# IAIf1Doc.net
KiCad netlist of a schematic drawn in Altium Designer
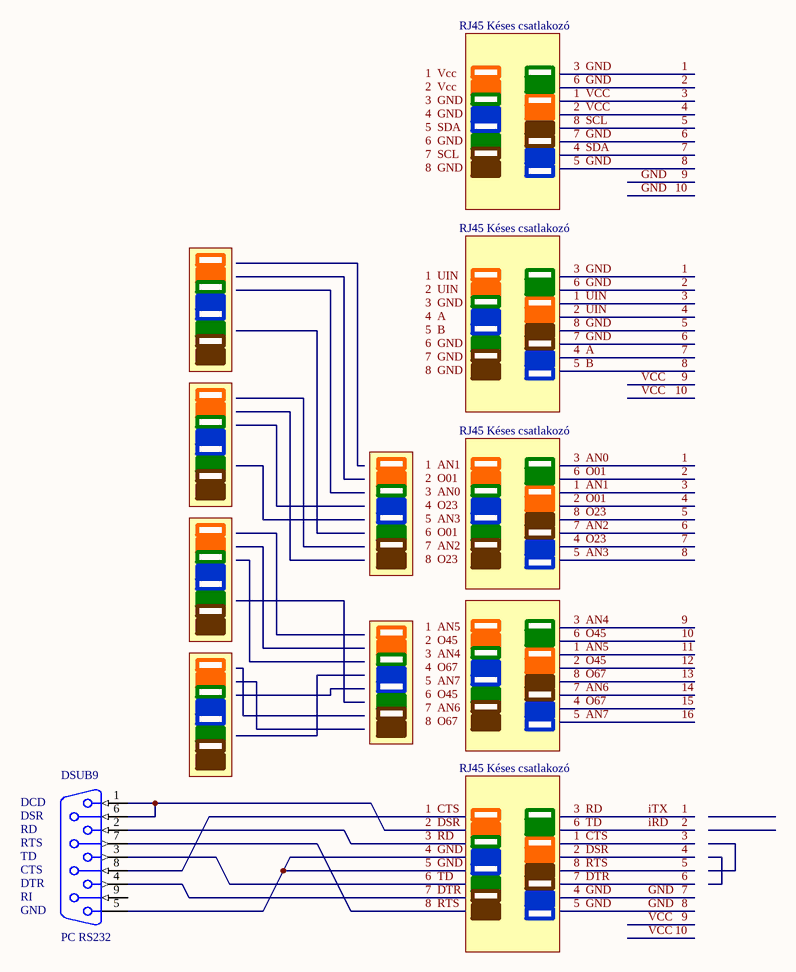
[diagram p0: IAIf1Doc.SchDoc]

(export (version "E")
  (design (tool "Eeschema 10.0.6"))
  (components
    (comp (ref "DSUB9")
      (value "PC RS232")
      (footprint "DSUB1.385-2H9")
      (description "Receptacle Assembly, 9 Position, Right Angle")
      (fields (field (name "PUBLISHER") "Altium Limited"))
      (libsource (lib "Miscellaneous Connectors") (part "D Connector 9"))
    )
  )
  (nets
    (net (code "1") (name "/1") (class "Default")
      (node (ref "DSUB9") (pin "2") (pinfunction "2_2") (pintype "input"))
    )
    (net (code "2") (name "/1  AN1") (class "Default")
      (node (ref "DSUB9") (pin "8") (pinfunction "8_8") (pintype "input"))
    )
    (net (code "5") (name "/2") (class "Default")
      (node (ref "DSUB9") (pin "3") (pinfunction "3_3") (pintype "output"))
    )
    (net (code "6") (name "/2  DSR") (class "Default")
      (node (ref "DSUB9") (pin "1") (pinfunction "1_1") (pintype "input"))
      (node (ref "DSUB9") (pin "6") (pinfunction "6_6") (pintype "input"))
    )
    (net (code "8") (name "/5") (class "Default")
      (node (ref "DSUB9") (pin "7") (pinfunction "7_7") (pintype "output"))
    )
    (net (code "10") (name "/6") (class "Default")
      (node (ref "DSUB9") (pin "4") (pinfunction "4_4") (pintype "output"))
    )
    (net (code "12") (name "/10") (class "Default")
      (node (ref "DSUB9") (pin "5") (pinfunction "5_5") (pintype "power_in"))
    )
    (net (code "18") (name "unconnected-(DSUB9-Pad9)") (class "Default")
      (node (ref "DSUB9") (pin "9") (pinfunction "9_9") (pintype "input"))
    )
  )
)
